# stepper_w_2_input_bitsA.net
KiCad netlist of a schematic drawn in EAGLE
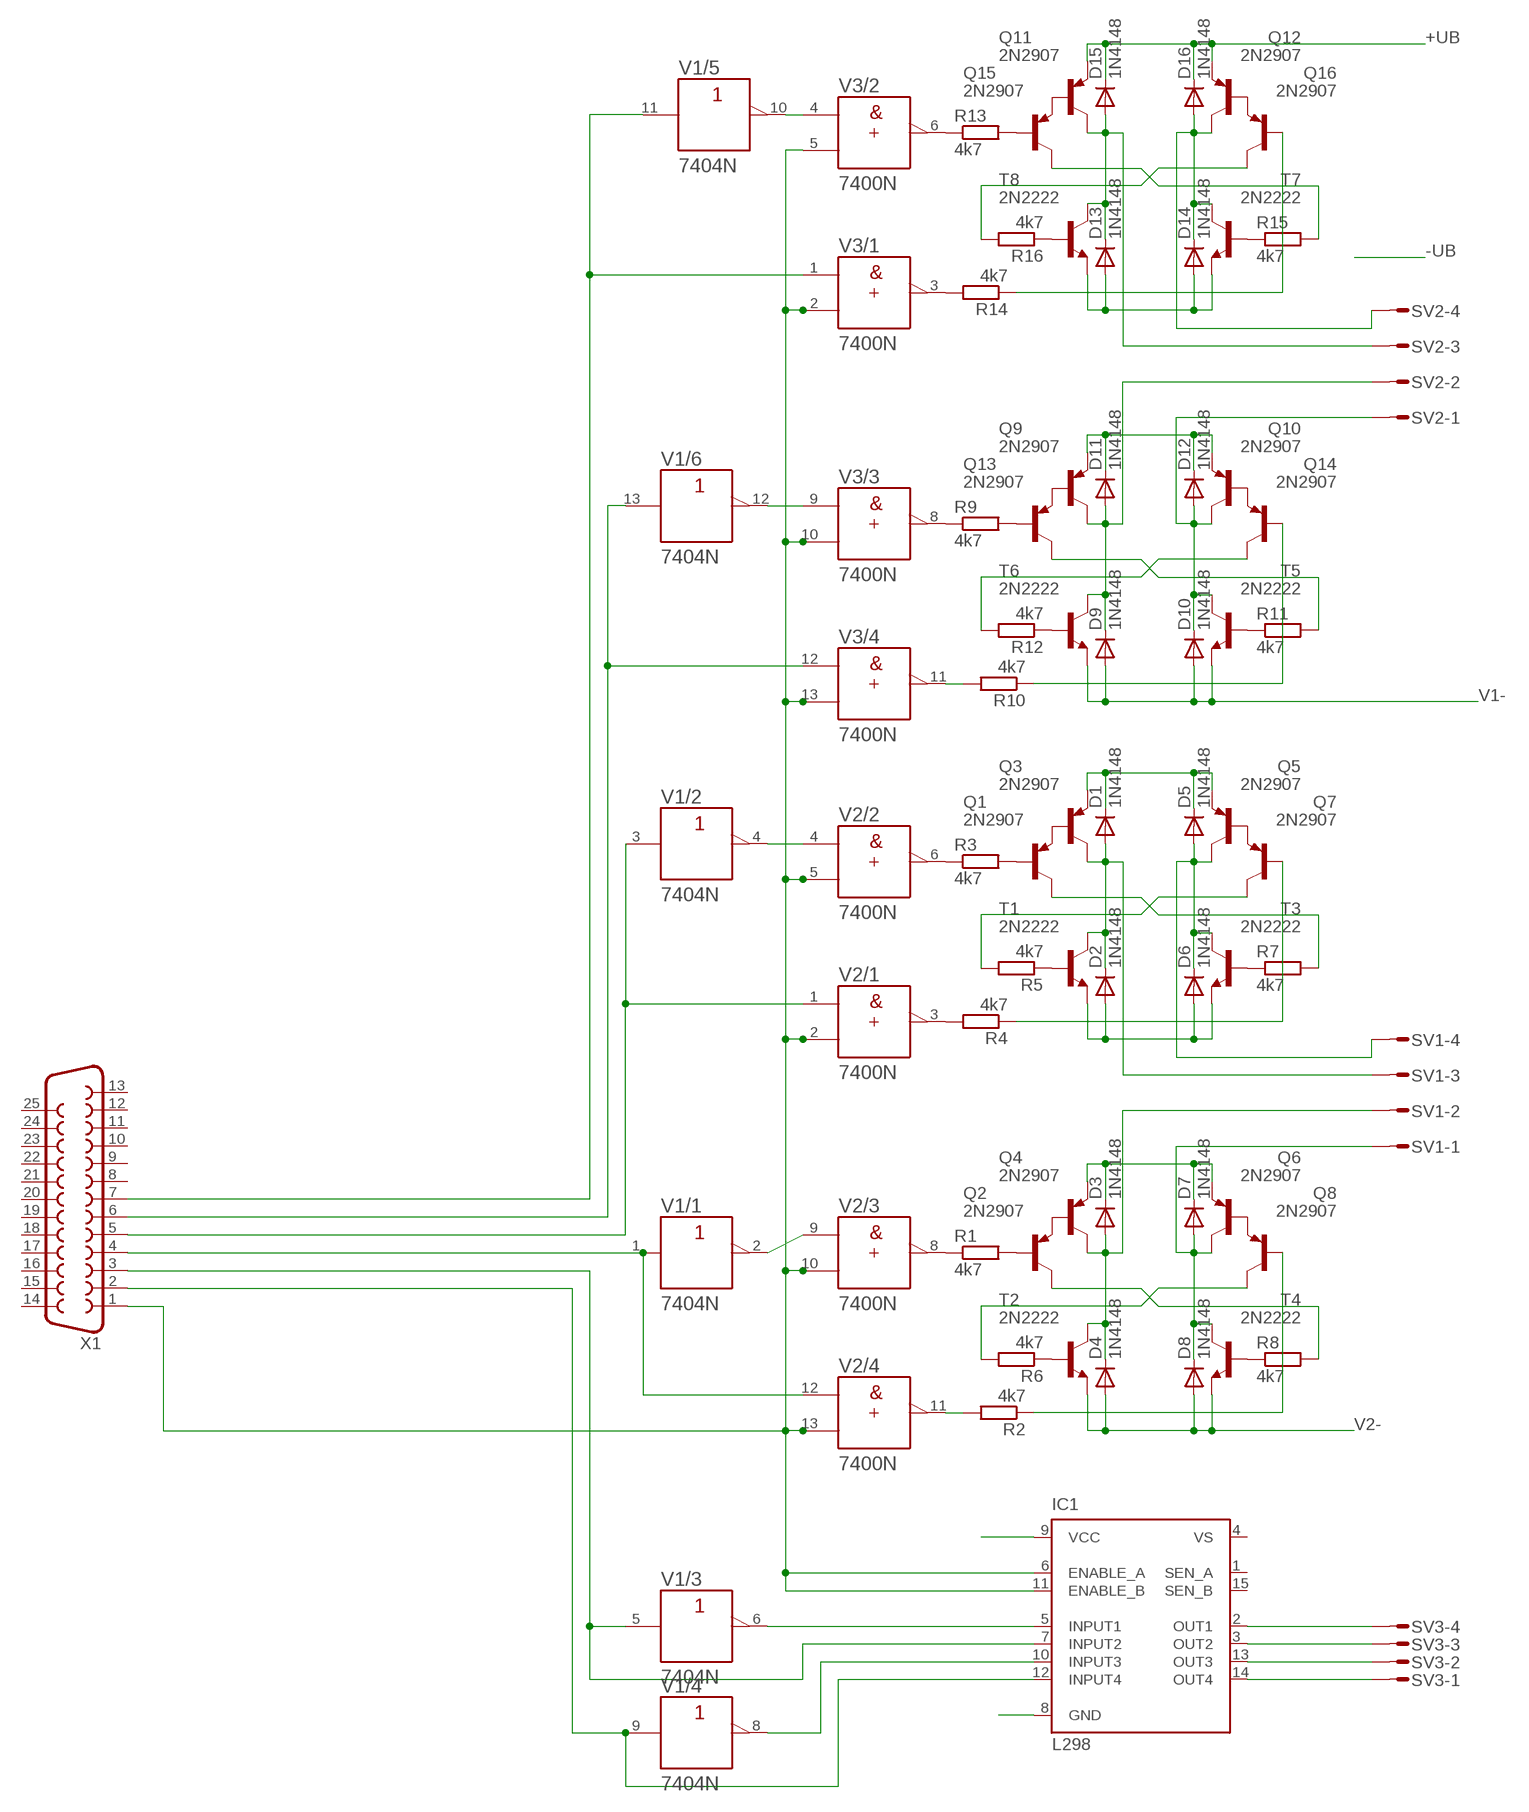
[diagram p0: schematic, sheet 1]

(export (version "E")
  (design (tool "Eeschema 10.0.6"))
  (components
    (comp (ref "D1")
      (value "1N4148")
      (footprint "eagle-import:D-2.5")
      (libsource (lib "eagle-import") (part "DIODE-D-2.5"))
    )
    (comp (ref "D2")
      (value "1N4148")
      (footprint "eagle-import:D-2.5")
      (libsource (lib "eagle-import") (part "DIODE-D-2.5"))
    )
    (comp (ref "D3")
      (value "1N4148")
      (footprint "eagle-import:D-2.5")
      (libsource (lib "eagle-import") (part "DIODE-D-2.5"))
    )
    (comp (ref "D4")
      (value "1N4148")
      (footprint "eagle-import:D-2.5")
      (libsource (lib "eagle-import") (part "DIODE-D-2.5"))
    )
    (comp (ref "D5")
      (value "1N4148")
      (footprint "eagle-import:D-2.5")
      (libsource (lib "eagle-import") (part "DIODE-D-2.5"))
    )
    (comp (ref "D6")
      (value "1N4148")
      (footprint "eagle-import:D-2.5")
      (libsource (lib "eagle-import") (part "DIODE-D-2.5"))
    )
    (comp (ref "D7")
      (value "1N4148")
      (footprint "eagle-import:D-2.5")
      (libsource (lib "eagle-import") (part "DIODE-D-2.5"))
    )
    (comp (ref "D8")
      (value "1N4148")
      (footprint "eagle-import:D-2.5")
      (libsource (lib "eagle-import") (part "DIODE-D-2.5"))
    )
    (comp (ref "D9")
      (value "1N4148")
      (footprint "eagle-import:D-2.5")
      (libsource (lib "eagle-import") (part "DIODE-D-2.5"))
    )
    (comp (ref "D10")
      (value "1N4148")
      (footprint "eagle-import:D-2.5")
      (libsource (lib "eagle-import") (part "DIODE-D-2.5"))
    )
    (comp (ref "D11")
      (value "1N4148")
      (footprint "eagle-import:D-2.5")
      (libsource (lib "eagle-import") (part "DIODE-D-2.5"))
    )
    (comp (ref "D12")
      (value "1N4148")
      (footprint "eagle-import:D-2.5")
      (libsource (lib "eagle-import") (part "DIODE-D-2.5"))
    )
    (comp (ref "D13")
      (value "1N4148")
      (footprint "eagle-import:D-2.5")
      (libsource (lib "eagle-import") (part "DIODE-D-2.5"))
    )
    (comp (ref "D14")
      (value "1N4148")
      (footprint "eagle-import:D-2.5")
      (libsource (lib "eagle-import") (part "DIODE-D-2.5"))
    )
    (comp (ref "D15")
      (value "1N4148")
      (footprint "eagle-import:D-2.5")
      (libsource (lib "eagle-import") (part "DIODE-D-2.5"))
    )
    (comp (ref "D16")
      (value "1N4148")
      (footprint "eagle-import:D-2.5")
      (libsource (lib "eagle-import") (part "DIODE-D-2.5"))
    )
    (comp (ref "IC1")
      (value "L298")
      (footprint "eagle-import:MULTIWATT-15")
      (fields (field (name "MPN") "L298N"))
      (libsource (lib "eagle-import") (part "L298"))
    )
    (comp (ref "Q1")
      (value "2N2907")
      (footprint "eagle-import:TO18")
      (libsource (lib "eagle-import") (part "2N2907"))
    )
    (comp (ref "Q2")
      (value "2N2907")
      (footprint "eagle-import:TO18")
      (libsource (lib "eagle-import") (part "2N2907"))
    )
    (comp (ref "Q3")
      (value "2N2907")
      (footprint "eagle-import:TO18")
      (libsource (lib "eagle-import") (part "2N2907"))
    )
    (comp (ref "Q4")
      (value "2N2907")
      (footprint "eagle-import:TO18")
      (libsource (lib "eagle-import") (part "2N2907"))
    )
    (comp (ref "Q5")
      (value "2N2907")
      (footprint "eagle-import:TO18")
      (libsource (lib "eagle-import") (part "2N2907"))
    )
    (comp (ref "Q6")
      (value "2N2907")
      (footprint "eagle-import:TO18")
      (libsource (lib "eagle-import") (part "2N2907"))
    )
    (comp (ref "Q7")
      (value "2N2907")
      (footprint "eagle-import:TO18")
      (libsource (lib "eagle-import") (part "2N2907"))
    )
    (comp (ref "Q8")
      (value "2N2907")
      (footprint "eagle-import:TO18")
      (libsource (lib "eagle-import") (part "2N2907"))
    )
    (comp (ref "Q9")
      (value "2N2907")
      (footprint "eagle-import:TO18")
      (libsource (lib "eagle-import") (part "2N2907"))
    )
    (comp (ref "Q10")
      (value "2N2907")
      (footprint "eagle-import:TO18")
      (libsource (lib "eagle-import") (part "2N2907"))
    )
    (comp (ref "Q11")
      (value "2N2907")
      (footprint "eagle-import:TO18")
      (libsource (lib "eagle-import") (part "2N2907"))
    )
    (comp (ref "Q12")
      (value "2N2907")
      (footprint "eagle-import:TO18")
      (libsource (lib "eagle-import") (part "2N2907"))
    )
    (comp (ref "Q13")
      (value "2N2907")
      (footprint "eagle-import:TO18")
      (libsource (lib "eagle-import") (part "2N2907"))
    )
    (comp (ref "Q14")
      (value "2N2907")
      (footprint "eagle-import:TO18")
      (libsource (lib "eagle-import") (part "2N2907"))
    )
    (comp (ref "Q15")
      (value "2N2907")
      (footprint "eagle-import:TO18")
      (libsource (lib "eagle-import") (part "2N2907"))
    )
    (comp (ref "Q16")
      (value "2N2907")
      (footprint "eagle-import:TO18")
      (libsource (lib "eagle-import") (part "2N2907"))
    )
    (comp (ref "R1")
      (value "4k7")
      (footprint "eagle-import:0204_7")
      (libsource (lib "eagle-import") (part "R-EU_0204/7"))
    )
    (comp (ref "R2")
      (value "4k7")
      (footprint "eagle-import:0207_10")
      (libsource (lib "eagle-import") (part "R-EU_0207/10"))
    )
    (comp (ref "R3")
      (value "4k7")
      (footprint "eagle-import:0207_10")
      (libsource (lib "eagle-import") (part "R-EU_0207/10"))
    )
    (comp (ref "R4")
      (value "4k7")
      (footprint "eagle-import:0207_10")
      (libsource (lib "eagle-import") (part "R-EU_0207/10"))
    )
    (comp (ref "R5")
      (value "4k7")
      (footprint "eagle-import:0207_10")
      (libsource (lib "eagle-import") (part "R-EU_0207/10"))
    )
    (comp (ref "R6")
      (value "4k7")
      (footprint "eagle-import:0207_10")
      (libsource (lib "eagle-import") (part "R-EU_0207/10"))
    )
    (comp (ref "R7")
      (value "4k7")
      (footprint "eagle-import:0207_10")
      (libsource (lib "eagle-import") (part "R-EU_0207/10"))
    )
    (comp (ref "R8")
      (value "4k7")
      (footprint "eagle-import:0207_10")
      (libsource (lib "eagle-import") (part "R-EU_0207/10"))
    )
    (comp (ref "R9")
      (value "4k7")
      (footprint "eagle-import:0204_7")
      (libsource (lib "eagle-import") (part "R-EU_0204/7"))
    )
    (comp (ref "R10")
      (value "4k7")
      (footprint "eagle-import:0207_10")
      (libsource (lib "eagle-import") (part "R-EU_0207/10"))
    )
    (comp (ref "R11")
      (value "4k7")
      (footprint "eagle-import:0207_10")
      (libsource (lib "eagle-import") (part "R-EU_0207/10"))
    )
    (comp (ref "R12")
      (value "4k7")
      (footprint "eagle-import:0207_10")
      (libsource (lib "eagle-import") (part "R-EU_0207/10"))
    )
    (comp (ref "R13")
      (value "4k7")
      (footprint "eagle-import:0207_10")
      (libsource (lib "eagle-import") (part "R-EU_0207/10"))
    )
    (comp (ref "R14")
      (value "4k7")
      (footprint "eagle-import:0207_10")
      (libsource (lib "eagle-import") (part "R-EU_0207/10"))
    )
    (comp (ref "R15")
      (value "4k7")
      (footprint "eagle-import:0207_10")
      (libsource (lib "eagle-import") (part "R-EU_0207/10"))
    )
    (comp (ref "R16")
      (value "4k7")
      (footprint "eagle-import:0207_10")
      (libsource (lib "eagle-import") (part "R-EU_0207/10"))
    )
    (comp (ref "SV1")
      (value "S04P")
      (footprint "eagle-import:S04P")
      (libsource (lib "eagle-import") (part "S04P"))
    )
    (comp (ref "SV2")
      (value "S04P")
      (footprint "eagle-import:S04P")
      (libsource (lib "eagle-import") (part "S04P"))
    )
    (comp (ref "SV3")
      (value "S04P")
      (footprint "eagle-import:S04P")
      (libsource (lib "eagle-import") (part "S04P"))
    )
    (comp (ref "T1")
      (value "2N2222")
      (footprint "eagle-import:TO18")
      (libsource (lib "eagle-import") (part "2N2222"))
    )
    (comp (ref "T2")
      (value "2N2222")
      (footprint "eagle-import:TO18")
      (libsource (lib "eagle-import") (part "2N2222"))
    )
    (comp (ref "T3")
      (value "2N2222")
      (footprint "eagle-import:TO18")
      (libsource (lib "eagle-import") (part "2N2222"))
    )
    (comp (ref "T4")
      (value "2N2222")
      (footprint "eagle-import:TO18")
      (libsource (lib "eagle-import") (part "2N2222"))
    )
    (comp (ref "T5")
      (value "2N2222")
      (footprint "eagle-import:TO18")
      (libsource (lib "eagle-import") (part "2N2222"))
    )
    (comp (ref "T6")
      (value "2N2222")
      (footprint "eagle-import:TO18")
      (libsource (lib "eagle-import") (part "2N2222"))
    )
    (comp (ref "T7")
      (value "2N2222")
      (footprint "eagle-import:TO18")
      (libsource (lib "eagle-import") (part "2N2222"))
    )
    (comp (ref "T8")
      (value "2N2222")
      (footprint "eagle-import:TO18")
      (libsource (lib "eagle-import") (part "2N2222"))
    )
    (comp (ref "V1")
      (value "7404N")
      (footprint "eagle-import:DIL14")
      (libsource (lib "eagle-import") (part "7404N"))
    )
    (comp (ref "V2")
      (value "7400N")
      (footprint "eagle-import:DIL14")
      (libsource (lib "eagle-import") (part "7400N"))
    )
    (comp (ref "V3")
      (value "7400N")
      (footprint "eagle-import:DIL14")
      (libsource (lib "eagle-import") (part "7400N"))
    )
    (comp (ref "X1")
      (value "F25HP")
      (footprint "eagle-import:F25HP")
      (libsource (lib "eagle-import") (part "F25HP"))
    )
  )
  (nets
    (net (code "1") (name "/+UB") (class "Default")
      (node (ref "D1") (pin "C") (pinfunction "C_C") (pintype "passive"))
      (node (ref "D11") (pin "C") (pinfunction "C_C") (pintype "passive"))
      (node (ref "D12") (pin "C") (pinfunction "C_C") (pintype "passive"))
      (node (ref "D15") (pin "C") (pinfunction "C_C") (pintype "passive"))
      (node (ref "D16") (pin "C") (pinfunction "C_C") (pintype "passive"))
      (node (ref "D3") (pin "C") (pinfunction "C_C") (pintype "passive"))
      (node (ref "D5") (pin "C") (pinfunction "C_C") (pintype "passive"))
      (node (ref "D7") (pin "C") (pinfunction "C_C") (pintype "passive"))
      (node (ref "IC1") (pin "9") (pinfunction "VCC_9") (pintype "power_in"))
      (node (ref "Q10") (pin "1") (pinfunction "E_1") (pintype "passive"))
      (node (ref "Q11") (pin "1") (pinfunction "E_1") (pintype "passive"))
      (node (ref "Q12") (pin "1") (pinfunction "E_1") (pintype "passive"))
      (node (ref "Q3") (pin "1") (pinfunction "E_1") (pintype "passive"))
      (node (ref "Q4") (pin "1") (pinfunction "E_1") (pintype "passive"))
      (node (ref "Q5") (pin "1") (pinfunction "E_1") (pintype "passive"))
      (node (ref "Q6") (pin "1") (pinfunction "E_1") (pintype "passive"))
      (node (ref "Q9") (pin "1") (pinfunction "E_1") (pintype "passive"))
    )
    (net (code "2") (name "/-UB") (class "Default")
      (node (ref "IC1") (pin "8") (pinfunction "GND_8") (pintype "power_in"))
    )
    (net (code "3") (name "/V1-") (class "Default")
      (node (ref "D10") (pin "A") (pinfunction "A_A") (pintype "passive"))
      (node (ref "D13") (pin "A") (pinfunction "A_A") (pintype "passive"))
      (node (ref "D14") (pin "A") (pinfunction "A_A") (pintype "passive"))
      (node (ref "D9") (pin "A") (pinfunction "A_A") (pintype "passive"))
      (node (ref "T5") (pin "1") (pinfunction "E_1") (pintype "passive"))
      (node (ref "T6") (pin "1") (pinfunction "E_1") (pintype "passive"))
      (node (ref "T7") (pin "1") (pinfunction "E_1") (pintype "passive"))
      (node (ref "T8") (pin "1") (pinfunction "E_1") (pintype "passive"))
    )
    (net (code "4") (name "/V2-") (class "Default")
      (node (ref "D2") (pin "A") (pinfunction "A_A") (pintype "passive"))
      (node (ref "D4") (pin "A") (pinfunction "A_A") (pintype "passive"))
      (node (ref "D6") (pin "A") (pinfunction "A_A") (pintype "passive"))
      (node (ref "D8") (pin "A") (pinfunction "A_A") (pintype "passive"))
      (node (ref "T1") (pin "1") (pinfunction "E_1") (pintype "passive"))
      (node (ref "T2") (pin "1") (pinfunction "E_1") (pintype "passive"))
      (node (ref "T3") (pin "1") (pinfunction "E_1") (pintype "passive"))
      (node (ref "T4") (pin "1") (pinfunction "E_1") (pintype "passive"))
    )
    (net (code "5") (name "/VS") (class "Default")
      (node (ref "IC1") (pin "4") (pinfunction "VS_4") (pintype "power_in"))
    )
    (net (code "6") (name "Net-(IC1-ENABLE_A)") (class "Default")
      (node (ref "IC1") (pin "11") (pinfunction "ENABLE_B_11") (pintype "input"))
      (node (ref "IC1") (pin "6") (pinfunction "ENABLE_A_6") (pintype "input"))
      (node (ref "V2") (pin "10") (pinfunction "B_10") (pintype "input"))
      (node (ref "V2") (pin "13") (pinfunction "B_13") (pintype "input"))
      (node (ref "V2") (pin "2") (pinfunction "B_2") (pintype "input"))
      (node (ref "V2") (pin "5") (pinfunction "B_5") (pintype "input"))
      (node (ref "V3") (pin "10") (pinfunction "B_10") (pintype "input"))
      (node (ref "V3") (pin "13") (pinfunction "B_13") (pintype "input"))
      (node (ref "V3") (pin "2") (pinfunction "B_2") (pintype "input"))
      (node (ref "V3") (pin "5") (pinfunction "B_5") (pintype "input"))
      (node (ref "X1") (pin "1") (pinfunction "1_1") (pintype "passive"))
    )
    (net (code "7") (name "Net-(IC1-INPUT1)") (class "Default")
      (node (ref "IC1") (pin "5") (pinfunction "INPUT1_5") (pintype "input"))
      (node (ref "V1") (pin "6") (pinfunction "Y_6") (pintype "output"))
    )
    (net (code "8") (name "Net-(IC1-INPUT2)") (class "Default")
      (node (ref "IC1") (pin "7") (pinfunction "INPUT2_7") (pintype "input"))
      (node (ref "V1") (pin "5") (pinfunction "A_5") (pintype "input"))
      (node (ref "X1") (pin "3") (pinfunction "3_3") (pintype "passive"))
    )
    (net (code "9") (name "Net-(IC1-INPUT3)") (class "Default")
      (node (ref "IC1") (pin "10") (pinfunction "INPUT3_10") (pintype "input"))
      (node (ref "V1") (pin "8") (pinfunction "Y_8") (pintype "output"))
    )
    (net (code "10") (name "Net-(IC1-INPUT4)") (class "Default")
      (node (ref "IC1") (pin "12") (pinfunction "INPUT4_12") (pintype "input"))
      (node (ref "V1") (pin "9") (pinfunction "A_9") (pintype "input"))
      (node (ref "X1") (pin "2") (pinfunction "2_2") (pintype "passive"))
    )
    (net (code "11") (name "Net-(IC1-OUT1)") (class "Default")
      (node (ref "IC1") (pin "2") (pinfunction "OUT1_2") (pintype "output"))
      (node (ref "SV3") (pin "4") (pinfunction "S_4") (pintype "passive"))
    )
    (net (code "12") (name "Net-(IC1-OUT2)") (class "Default")
      (node (ref "IC1") (pin "3") (pinfunction "OUT2_3") (pintype "output"))
      (node (ref "SV3") (pin "3") (pinfunction "S_3") (pintype "passive"))
    )
    (net (code "13") (name "Net-(IC1-OUT3)") (class "Default")
      (node (ref "IC1") (pin "13") (pinfunction "OUT3_13") (pintype "output"))
      (node (ref "SV3") (pin "2") (pinfunction "S_2") (pintype "passive"))
    )
    (net (code "14") (name "Net-(IC1-OUT4)") (class "Default")
      (node (ref "IC1") (pin "14") (pinfunction "OUT4_14") (pintype "output"))
      (node (ref "SV3") (pin "1") (pinfunction "S_1") (pintype "passive"))
    )
    (net (code "15") (name "Net-(Q1-B)") (class "Default")
      (node (ref "Q1") (pin "2") (pinfunction "B_2") (pintype "passive"))
      (node (ref "R3") (pin "2") (pinfunction "2_2") (pintype "passive"))
    )
    (net (code "16") (name "Net-(Q1-C)") (class "Default")
      (node (ref "Q1") (pin "3") (pinfunction "C_3") (pintype "passive"))
      (node (ref "R7") (pin "2") (pinfunction "2_2") (pintype "passive"))
    )
    (net (code "17") (name "Net-(Q1-E)") (class "Default")
      (node (ref "Q1") (pin "1") (pinfunction "E_1") (pintype "passive"))
      (node (ref "Q3") (pin "2") (pinfunction "B_2") (pintype "passive"))
    )
    (net (code "18") (name "Net-(Q2-B)") (class "Default")
      (node (ref "Q2") (pin "2") (pinfunction "B_2") (pintype "passive"))
      (node (ref "R1") (pin "2") (pinfunction "2_2") (pintype "passive"))
    )
    (net (code "19") (name "Net-(Q2-C)") (class "Default")
      (node (ref "Q2") (pin "3") (pinfunction "C_3") (pintype "passive"))
      (node (ref "R8") (pin "2") (pinfunction "2_2") (pintype "passive"))
    )
    (net (code "20") (name "Net-(Q2-E)") (class "Default")
      (node (ref "Q2") (pin "1") (pinfunction "E_1") (pintype "passive"))
      (node (ref "Q4") (pin "2") (pinfunction "B_2") (pintype "passive"))
    )
    (net (code "21") (name "Net-(Q3-C)") (class "Default")
      (node (ref "D1") (pin "A") (pinfunction "A_A") (pintype "passive"))
      (node (ref "D2") (pin "C") (pinfunction "C_C") (pintype "passive"))
      (node (ref "Q3") (pin "3") (pinfunction "C_3") (pintype "passive"))
      (node (ref "SV1") (pin "3") (pinfunction "S_3") (pintype "passive"))
      (node (ref "T1") (pin "3") (pinfunction "C_3") (pintype "passive"))
    )
    (net (code "22") (name "Net-(Q4-C)") (class "Default")
      (node (ref "D3") (pin "A") (pinfunction "A_A") (pintype "passive"))
      (node (ref "D4") (pin "C") (pinfunction "C_C") (pintype "passive"))
      (node (ref "Q4") (pin "3") (pinfunction "C_3") (pintype "passive"))
      (node (ref "SV1") (pin "2") (pinfunction "S_2") (pintype "passive"))
      (node (ref "T2") (pin "3") (pinfunction "C_3") (pintype "passive"))
    )
    (net (code "23") (name "Net-(Q5-B)") (class "Default")
      (node (ref "Q5") (pin "2") (pinfunction "B_2") (pintype "passive"))
      (node (ref "Q7") (pin "1") (pinfunction "E_1") (pintype "passive"))
    )
    (net (code "24") (name "Net-(Q5-C)") (class "Default")
      (node (ref "D5") (pin "A") (pinfunction "A_A") (pintype "passive"))
      (node (ref "D6") (pin "C") (pinfunction "C_C") (pintype "passive"))
      (node (ref "Q5") (pin "3") (pinfunction "C_3") (pintype "passive"))
      (node (ref "SV1") (pin "4") (pinfunction "S_4") (pintype "passive"))
      (node (ref "T3") (pin "3") (pinfunction "C_3") (pintype "passive"))
    )
    (net (code "25") (name "Net-(Q6-B)") (class "Default")
      (node (ref "Q6") (pin "2") (pinfunction "B_2") (pintype "passive"))
      (node (ref "Q8") (pin "1") (pinfunction "E_1") (pintype "passive"))
    )
    (net (code "26") (name "Net-(Q6-C)") (class "Default")
      (node (ref "D7") (pin "A") (pinfunction "A_A") (pintype "passive"))
      (node (ref "D8") (pin "C") (pinfunction "C_C") (pintype "passive"))
      (node (ref "Q6") (pin "3") (pinfunction "C_3") (pintype "passive"))
      (node (ref "SV1") (pin "1") (pinfunction "S_1") (pintype "passive"))
      (node (ref "T4") (pin "3") (pinfunction "C_3") (pintype "passive"))
    )
    (net (code "27") (name "Net-(Q7-B)") (class "Default")
      (node (ref "Q7") (pin "2") (pinfunction "B_2") (pintype "passive"))
      (node (ref "R4") (pin "1") (pinfunction "1_1") (pintype "passive"))
    )
    (net (code "28") (name "Net-(Q7-C)") (class "Default")
      (node (ref "Q7") (pin "3") (pinfunction "C_3") (pintype "passive"))
      (node (ref "R5") (pin "2") (pinfunction "2_2") (pintype "passive"))
    )
    (net (code "29") (name "Net-(Q8-B)") (class "Default")
      (node (ref "Q8") (pin "2") (pinfunction "B_2") (pintype "passive"))
      (node (ref "R2") (pin "1") (pinfunction "1_1") (pintype "passive"))
    )
    (net (code "30") (name "Net-(Q8-C)") (class "Default")
      (node (ref "Q8") (pin "3") (pinfunction "C_3") (pintype "passive"))
      (node (ref "R6") (pin "2") (pinfunction "2_2") (pintype "passive"))
    )
    (net (code "31") (name "Net-(Q9-C)") (class "Default")
      (node (ref "D11") (pin "A") (pinfunction "A_A") (pintype "passive"))
      (node (ref "D9") (pin "C") (pinfunction "C_C") (pintype "passive"))
      (node (ref "Q9") (pin "3") (pinfunction "C_3") (pintype "passive"))
      (node (ref "SV2") (pin "2") (pinfunction "S_2") (pintype "passive"))
      (node (ref "T6") (pin "3") (pinfunction "C_3") (pintype "passive"))
    )
    (net (code "32") (name "Net-(Q10-B)") (class "Default")
      (node (ref "Q10") (pin "2") (pinfunction "B_2") (pintype "passive"))
      (node (ref "Q14") (pin "1") (pinfunction "E_1") (pintype "passive"))
    )
    (net (code "33") (name "Net-(Q10-C)") (class "Default")
      (node (ref "D10") (pin "C") (pinfunction "C_C") (pintype "passive"))
      (node (ref "D12") (pin "A") (pinfunction "A_A") (pintype "passive"))
      (node (ref "Q10") (pin "3") (pinfunction "C_3") (pintype "passive"))
      (node (ref "SV2") (pin "1") (pinfunction "S_1") (pintype "passive"))
      (node (ref "T5") (pin "3") (pinfunction "C_3") (pintype "passive"))
    )
    (net (code "34") (name "Net-(Q11-B)") (class "Default")
      (node (ref "Q11") (pin "2") (pinfunction "B_2") (pintype "passive"))
      (node (ref "Q15") (pin "1") (pinfunction "E_1") (pintype "passive"))
    )
    (net (code "35") (name "Net-(Q11-C)") (class "Default")
      (node (ref "D13") (pin "C") (pinfunction "C_C") (pintype "passive"))
      (node (ref "D15") (pin "A") (pinfunction "A_A") (pintype "passive"))
      (node (ref "Q11") (pin "3") (pinfunction "C_3") (pintype "passive"))
      (node (ref "SV2") (pin "3") (pinfunction "S_3") (pintype "passive"))
      (node (ref "T8") (pin "3") (pinfunction "C_3") (pintype "passive"))
    )
    (net (code "36") (name "Net-(Q12-B)") (class "Default")
      (node (ref "Q12") (pin "2") (pinfunction "B_2") (pintype "passive"))
      (node (ref "Q16") (pin "1") (pinfunction "E_1") (pintype "passive"))
    )
    (net (code "37") (name "Net-(Q12-C)") (class "Default")
      (node (ref "D14") (pin "C") (pinfunction "C_C") (pintype "passive"))
      (node (ref "D16") (pin "A") (pinfunction "A_A") (pintype "passive"))
      (node (ref "Q12") (pin "3") (pinfunction "C_3") (pintype "passive"))
      (node (ref "SV2") (pin "4") (pinfunction "S_4") (pintype "passive"))
      (node (ref "T7") (pin "3") (pinfunction "C_3") (pintype "passive"))
    )
    (net (code "38") (name "Net-(Q13-B)") (class "Default")
      (node (ref "Q13") (pin "2") (pinfunction "B_2") (pintype "passive"))
      (node (ref "R9") (pin "2") (pinfunction "2_2") (pintype "passive"))
    )
    (net (code "39") (name "Net-(Q13-C)") (class "Default")
      (node (ref "Q13") (pin "3") (pinfunction "C_3") (pintype "passive"))
      (node (ref "R11") (pin "2") (pinfunction "2_2") (pintype "passive"))
    )
    (net (code "40") (name "Net-(Q13-E)") (class "Default")
      (node (ref "Q13") (pin "1") (pinfunction "E_1") (pintype "passive"))
      (node (ref "Q9") (pin "2") (pinfunction "B_2") (pintype "passive"))
    )
    (net (code "41") (name "Net-(Q14-B)") (class "Default")
      (node (ref "Q14") (pin "2") (pinfunction "B_2") (pintype "passive"))
      (node (ref "R10") (pin "1") (pinfunction "1_1") (pintype "passive"))
    )
    (net (code "42") (name "Net-(Q14-C)") (class "Default")
      (node (ref "Q14") (pin "3") (pinfunction "C_3") (pintype "passive"))
      (node (ref "R12") (pin "2") (pinfunction "2_2") (pintype "passive"))
    )
    (net (code "43") (name "Net-(Q15-B)") (class "Default")
      (node (ref "Q15") (pin "2") (pinfunction "B_2") (pintype "passive"))
      (node (ref "R13") (pin "2") (pinfunction "2_2") (pintype "passive"))
    )
    (net (code "44") (name "Net-(Q15-C)") (class "Default")
      (node (ref "Q15") (pin "3") (pinfunction "C_3") (pintype "passive"))
      (node (ref "R15") (pin "2") (pinfunction "2_2") (pintype "passive"))
    )
    (net (code "45") (name "Net-(Q16-B)") (class "Default")
      (node (ref "Q16") (pin "2") (pinfunction "B_2") (pintype "passive"))
      (node (ref "R14") (pin "1") (pinfunction "1_1") (pintype "passive"))
    )
    (net (code "46") (name "Net-(Q16-C)") (class "Default")
      (node (ref "Q16") (pin "3") (pinfunction "C_3") (pintype "passive"))
      (node (ref "R16") (pin "2") (pinfunction "2_2") (pintype "passive"))
    )
    (net (code "47") (name "Net-(T1-B)") (class "Default")
      (node (ref "R5") (pin "1") (pinfunction "1_1") (pintype "passive"))
      (node (ref "T1") (pin "2") (pinfunction "B_2") (pintype "passive"))
    )
    (net (code "48") (name "Net-(T2-B)") (class "Default")
      (node (ref "R6") (pin "1") (pinfunction "1_1") (pintype "passive"))
      (node (ref "T2") (pin "2") (pinfunction "B_2") (pintype "passive"))
    )
    (net (code "49") (name "Net-(T3-B)") (class "Default")
      (node (ref "R7") (pin "1") (pinfunction "1_1") (pintype "passive"))
      (node (ref "T3") (pin "2") (pinfunction "B_2") (pintype "passive"))
    )
    (net (code "50") (name "Net-(T4-B)") (class "Default")
      (node (ref "R8") (pin "1") (pinfunction "1_1") (pintype "passive"))
      (node (ref "T4") (pin "2") (pinfunction "B_2") (pintype "passive"))
    )
    (net (code "51") (name "Net-(T5-B)") (class "Default")
      (node (ref "R11") (pin "1") (pinfunction "1_1") (pintype "passive"))
      (node (ref "T5") (pin "2") (pinfunction "B_2") (pintype "passive"))
    )
    (net (code "52") (name "Net-(T6-B)") (class "Default")
      (node (ref "R12") (pin "1") (pinfunction "1_1") (pintype "passive"))
      (node (ref "T6") (pin "2") (pinfunction "B_2") (pintype "passive"))
    )
    (net (code "53") (name "Net-(T7-B)") (class "Default")
      (node (ref "R15") (pin "1") (pinfunction "1_1") (pintype "passive"))
      (node (ref "T7") (pin "2") (pinfunction "B_2") (pintype "passive"))
    )
    (net (code "54") (name "Net-(T8-B)") (class "Default")
      (node (ref "R16") (pin "1") (pinfunction "1_1") (pintype "passive"))
      (node (ref "T8") (pin "2") (pinfunction "B_2") (pintype "passive"))
    )
    (net (code "55") (name "Net-(V1C-A)") (class "Default")
      (node (ref "V1") (pin "1") (pinfunction "A_1") (pintype "input"))
      (node (ref "V2") (pin "12") (pinfunction "A_12") (pintype "input"))
      (node (ref "X1") (pin "4") (pinfunction "4_4") (pintype "passive"))
    )
    (net (code "56") (name "Net-(V1C-Y)") (class "Default")
      (node (ref "V1") (pin "2") (pinfunction "Y_2") (pintype "output"))
      (node (ref "V2") (pin "9") (pinfunction "A_9") (pintype "input"))
    )
    (net (code "57") (name "Net-(V1D-A)") (class "Default")
      (node (ref "V1") (pin "3") (pinfunction "A_3") (pintype "input"))
      (node (ref "V2") (pin "1") (pinfunction "A_1") (pintype "input"))
      (node (ref "X1") (pin "5") (pinfunction "5_5") (pintype "passive"))
    )
    (net (code "58") (name "Net-(V1D-Y)") (class "Default")
      (node (ref "V1") (pin "4") (pinfunction "Y_4") (pintype "output"))
      (node (ref "V2") (pin "4") (pinfunction "A_4") (pintype "input"))
    )
    (net (code "59") (name "Net-(V1G-A)") (class "Default")
      (node (ref "V1") (pin "11") (pinfunction "A_11") (pintype "input"))
      (node (ref "V3") (pin "1") (pinfunction "A_1") (pintype "input"))
      (node (ref "X1") (pin "7") (pinfunction "7_7") (pintype "passive"))
    )
    (net (code "60") (name "Net-(V1G-Y)") (class "Default")
      (node (ref "V1") (pin "10") (pinfunction "Y_10") (pintype "output"))
      (node (ref "V3") (pin "4") (pinfunction "A_4") (pintype "input"))
    )
    (net (code "61") (name "Net-(V1H-A)") (class "Default")
      (node (ref "V1") (pin "13") (pinfunction "A_13") (pintype "input"))
      (node (ref "V3") (pin "12") (pinfunction "A_12") (pintype "input"))
      (node (ref "X1") (pin "6") (pinfunction "6_6") (pintype "passive"))
    )
    (net (code "62") (name "Net-(V1H-Y)") (class "Default")
      (node (ref "V1") (pin "12") (pinfunction "Y_12") (pintype "output"))
      (node (ref "V3") (pin "9") (pinfunction "A_9") (pintype "input"))
    )
    (net (code "63") (name "Net-(V2C-Y)") (class "Default")
      (node (ref "R4") (pin "2") (pinfunction "2_2") (pintype "passive"))
      (node (ref "V2") (pin "3") (pinfunction "Y_3") (pintype "output"))
    )
    (net (code "64") (name "Net-(V2D-Y)") (class "Default")
      (node (ref "R3") (pin "1") (pinfunction "1_1") (pintype "passive"))
      (node (ref "V2") (pin "6") (pinfunction "Y_6") (pintype "output"))
    )
    (net (code "65") (name "Net-(V2E-Y)") (class "Default")
      (node (ref "R1") (pin "1") (pinfunction "1_1") (pintype "passive"))
      (node (ref "V2") (pin "8") (pinfunction "Y_8") (pintype "output"))
    )
    (net (code "66") (name "Net-(V2F-Y)") (class "Default")
      (node (ref "R2") (pin "2") (pinfunction "2_2") (pintype "passive"))
      (node (ref "V2") (pin "11") (pinfunction "Y_11") (pintype "output"))
    )
    (net (code "67") (name "Net-(V3C-Y)") (class "Default")
      (node (ref "R14") (pin "2") (pinfunction "2_2") (pintype "passive"))
      (node (ref "V3") (pin "3") (pinfunction "Y_3") (pintype "output"))
    )
    (net (code "68") (name "Net-(V3D-Y)") (class "Default")
      (node (ref "R13") (pin "1") (pinfunction "1_1") (pintype "passive"))
      (node (ref "V3") (pin "6") (pinfunction "Y_6") (pintype "output"))
    )
    (net (code "69") (name "Net-(V3E-Y)") (class "Default")
      (node (ref "R9") (pin "1") (pinfunction "1_1") (pintype "passive"))
      (node (ref "V3") (pin "8") (pinfunction "Y_8") (pintype "output"))
    )
    (net (code "70") (name "Net-(V3F-Y)") (class "Default")
      (node (ref "R10") (pin "2") (pinfunction "2_2") (pintype "passive"))
      (node (ref "V3") (pin "11") (pinfunction "Y_11") (pintype "output"))
    )
    (net (code "71") (name "unconnected-(IC1-SEN_A-Pad1)") (class "Default")
      (node (ref "IC1") (pin "1") (pinfunction "SEN_A_1") (pintype "input"))
    )
    (net (code "72") (name "unconnected-(IC1-SEN_B-Pad15)") (class "Default")
      (node (ref "IC1") (pin "15") (pinfunction "SEN_B_15") (pintype "input"))
    )
    (net (code "73") (name "unconnected-(X1-Pad8)") (class "Default")
      (node (ref "X1") (pin "8") (pinfunction "8_8") (pintype "passive"))
    )
    (net (code "74") (name "unconnected-(X1-Pad9)") (class "Default")
      (node (ref "X1") (pin "9") (pinfunction "9_9") (pintype "passive"))
    )
    (net (code "75") (name "unconnected-(X1-Pad10)") (class "Default")
      (node (ref "X1") (pin "10") (pinfunction "10_10") (pintype "passive"))
    )
    (net (code "76") (name "unconnected-(X1-Pad11)") (class "Default")
      (node (ref "X1") (pin "11") (pinfunction "11_11") (pintype "passive"))
    )
    (net (code "77") (name "unconnected-(X1-Pad12)") (class "Default")
      (node (ref "X1") (pin "12") (pinfunction "12_12") (pintype "passive"))
    )
    (net (code "78") (name "unconnected-(X1-Pad13)") (class "Default")
      (node (ref "X1") (pin "13") (pinfunction "13_13") (pintype "passive"))
    )
    (net (code "79") (name "unconnected-(X1-Pad14)") (class "Default")
      (node (ref "X1") (pin "14") (pinfunction "14_14") (pintype "passive"))
    )
    (net (code "80") (name "unconnected-(X1-Pad15)") (class "Default")
      (node (ref "X1") (pin "15") (pinfunction "15_15") (pintype "passive"))
    )
    (net (code "81") (name "unconnected-(X1-Pad16)") (class "Default")
      (node (ref "X1") (pin "16") (pinfunction "16_16") (pintype "passive"))
    )
    (net (code "82") (name "unconnected-(X1-Pad17)") (class "Default")
      (node (ref "X1") (pin "17") (pinfunction "17_17") (pintype "passive"))
    )
    (net (code "83") (name "unconnected-(X1-Pad18)") (class "Default")
      (node (ref "X1") (pin "18") (pinfunction "18_18") (pintype "passive"))
    )
    (net (code "84") (name "unconnected-(X1-Pad19)") (class "Default")
      (node (ref "X1") (pin "19") (pinfunction "19_19") (pintype "passive"))
    )
    (net (code "85") (name "unconnected-(X1-Pad20)") (class "Default")
      (node (ref "X1") (pin "20") (pinfunction "20_20") (pintype "passive"))
    )
    (net (code "86") (name "unconnected-(X1-Pad21)") (class "Default")
      (node (ref "X1") (pin "21") (pinfunction "21_21") (pintype "passive"))
    )
    (net (code "87") (name "unconnected-(X1-Pad22)") (class "Default")
      (node (ref "X1") (pin "22") (pinfunction "22_22") (pintype "passive"))
    )
    (net (code "88") (name "unconnected-(X1-Pad23)") (class "Default")
      (node (ref "X1") (pin "23") (pinfunction "23_23") (pintype "passive"))
    )
    (net (code "89") (name "unconnected-(X1-Pad24)") (class "Default")
      (node (ref "X1") (pin "24") (pinfunction "24_24") (pintype "passive"))
    )
    (net (code "90") (name "unconnected-(X1-Pad25)") (class "Default")
      (node (ref "X1") (pin "25") (pinfunction "25_25") (pintype "passive"))
    )
  )
)
